# mini_rotation.net
KiCad netlist of a schematic drawn in EAGLE
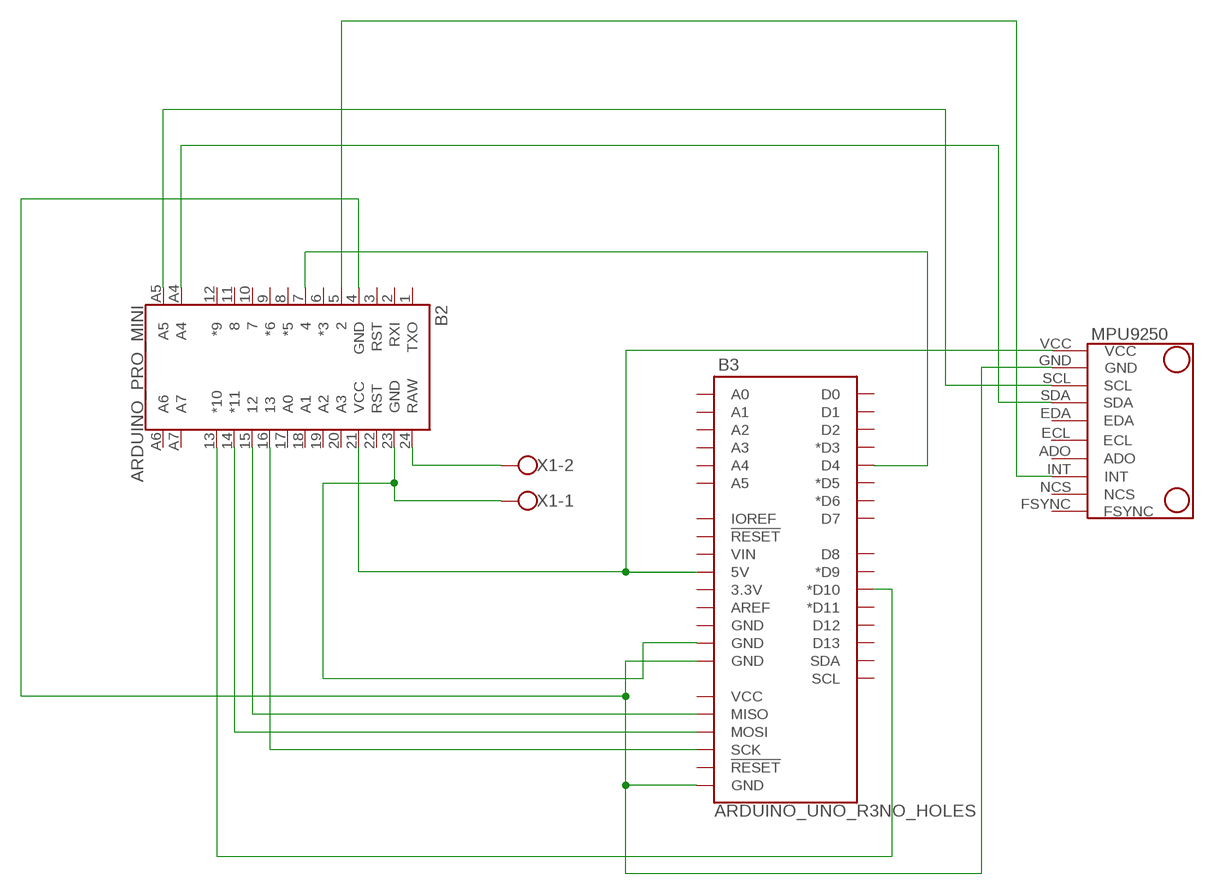
[diagram p0: schematic, sheet 1]

(export (version "E")
  (design (tool "Eeschema 10.0.6"))
  (components
    (comp (ref "B2")
      (value "ARDUINO_PRO_MINI")
      (footprint "eagle-import:ARDUINO_PRO_MINI")
      (libsource (lib "eagle-import") (part "ARDUINO_PRO_MINI"))
    )
    (comp (ref "B3")
      (value "ARDUINO_UNO_R3NO_HOLES")
      (footprint "eagle-import:ARDUINO_R3_NO_HOLES")
      (libsource (lib "eagle-import") (part "ARDUINO_UNO_R3NO_HOLES"))
    )
    (comp (ref "IC1")
      (value "MPU9250")
      (footprint "eagle-import:MPU9250")
      (libsource (lib "eagle-import") (part "MPU9250"))
    )
    (comp (ref "X1")
      (value "W237-102")
      (footprint "eagle-import:W237-102")
      (fields (field (name "MPN") "237-102"))
      (libsource (lib "eagle-import") (part "W237-102"))
    )
  )
  (nets
    (net (code "1") (name "Net-(B2-*10)") (class "Default")
      (node (ref "B2") (pin "13") (pinfunction "*10_13") (pintype "bidirectional"))
      (node (ref "B3") (pin "D10") (pinfunction "*D10_D10") (pintype "bidirectional"))
    )
    (net (code "2") (name "Net-(B2-*11)") (class "Default")
      (node (ref "B2") (pin "14") (pinfunction "*11_14") (pintype "bidirectional"))
      (node (ref "B3") (pin "MOSI") (pinfunction "MOSI_MOSI") (pintype "bidirectional"))
    )
    (net (code "3") (name "Net-(B2-2)") (class "Default")
      (node (ref "B2") (pin "5") (pinfunction "2_5") (pintype "bidirectional"))
      (node (ref "IC1") (pin "INT") (pinfunction "INT_INT") (pintype "bidirectional"))
    )
    (net (code "4") (name "Net-(B2-4)") (class "Default")
      (node (ref "B2") (pin "7") (pinfunction "4_7") (pintype "bidirectional"))
      (node (ref "B3") (pin "D4") (pinfunction "D4_D4") (pintype "bidirectional"))
    )
    (net (code "5") (name "Net-(B2-12)") (class "Default")
      (node (ref "B2") (pin "15") (pinfunction "12_15") (pintype "bidirectional"))
      (node (ref "B3") (pin "MISO") (pinfunction "MISO_MISO") (pintype "bidirectional"))
    )
    (net (code "6") (name "Net-(B2-13)") (class "Default")
      (node (ref "B2") (pin "16") (pinfunction "13_16") (pintype "bidirectional"))
      (node (ref "B3") (pin "SCK") (pinfunction "SCK_SCK") (pintype "bidirectional"))
    )
    (net (code "7") (name "Net-(B2-GND-Pad4)") (class "Default")
      (node (ref "B2") (pin "4") (pinfunction "GND_4") (pintype "power_in"))
      (node (ref "B3") (pin "GND@1") (pinfunction "GND_GND@1") (pintype "bidirectional"))
      (node (ref "B3") (pin "GND@2") (pinfunction "GND_GND@2") (pintype "bidirectional"))
      (node (ref "IC1") (pin "GND") (pinfunction "GND_GND") (pintype "bidirectional"))
    )
    (net (code "8") (name "Net-(B2-PadA4)") (class "Default")
      (node (ref "B2") (pin "A4") (pinfunction "A4_A4") (pintype "bidirectional"))
      (node (ref "IC1") (pin "SDA") (pinfunction "SDA_SDA") (pintype "bidirectional"))
    )
    (net (code "9") (name "Net-(B2-PadA5)") (class "Default")
      (node (ref "B2") (pin "A5") (pinfunction "A5_A5") (pintype "bidirectional"))
      (node (ref "IC1") (pin "SCL") (pinfunction "SCL_SCL") (pintype "bidirectional"))
    )
    (net (code "10") (name "Net-(B2-RAW)") (class "Default")
      (node (ref "B2") (pin "24") (pinfunction "RAW_24") (pintype "power_in"))
      (node (ref "X1") (pin "2") (pinfunction "KL_2") (pintype "passive"))
    )
    (net (code "11") (name "Net-(B2-VCC)") (class "Default")
      (node (ref "B2") (pin "21") (pinfunction "VCC_21") (pintype "power_in"))
      (node (ref "B3") (pin "5V") (pinfunction "5V_5V") (pintype "bidirectional"))
      (node (ref "IC1") (pin "VCC") (pinfunction "VCC_VCC") (pintype "bidirectional"))
    )
    (net (code "12") (name "Net-(X1A-KL)") (class "Default")
      (node (ref "B2") (pin "23") (pinfunction "GND_23") (pintype "power_in"))
      (node (ref "B3") (pin "GND@3") (pinfunction "GND_GND@3") (pintype "bidirectional"))
      (node (ref "X1") (pin "1") (pinfunction "KL_1") (pintype "passive"))
    )
    (net (code "13") (name "unconnected-(B2-*3-Pad6)") (class "Default")
      (node (ref "B2") (pin "6") (pinfunction "*3_6") (pintype "bidirectional"))
    )
    (net (code "14") (name "unconnected-(B2-*5-Pad8)") (class "Default")
      (node (ref "B2") (pin "8") (pinfunction "*5_8") (pintype "bidirectional"))
    )
    (net (code "15") (name "unconnected-(B2-*6-Pad9)") (class "Default")
      (node (ref "B2") (pin "9") (pinfunction "*6_9") (pintype "bidirectional"))
    )
    (net (code "16") (name "unconnected-(B2-*9-Pad12)") (class "Default")
      (node (ref "B2") (pin "12") (pinfunction "*9_12") (pintype "bidirectional"))
    )
    (net (code "17") (name "unconnected-(B2-7-Pad10)") (class "Default")
      (node (ref "B2") (pin "10") (pinfunction "7_10") (pintype "bidirectional"))
    )
    (net (code "18") (name "unconnected-(B2-8-Pad11)") (class "Default")
      (node (ref "B2") (pin "11") (pinfunction "8_11") (pintype "bidirectional"))
    )
    (net (code "19") (name "unconnected-(B2-A0-Pad17)") (class "Default")
      (node (ref "B2") (pin "17") (pinfunction "A0_17") (pintype "bidirectional"))
    )
    (net (code "20") (name "unconnected-(B2-A1-Pad18)") (class "Default")
      (node (ref "B2") (pin "18") (pinfunction "A1_18") (pintype "bidirectional"))
    )
    (net (code "21") (name "unconnected-(B2-A2-Pad19)") (class "Default")
      (node (ref "B2") (pin "19") (pinfunction "A2_19") (pintype "bidirectional"))
    )
    (net (code "22") (name "unconnected-(B2-A3-Pad20)") (class "Default")
      (node (ref "B2") (pin "20") (pinfunction "A3_20") (pintype "bidirectional"))
    )
    (net (code "23") (name "unconnected-(B2-PadA6)") (class "Default")
      (node (ref "B2") (pin "A6") (pinfunction "A6_A6") (pintype "bidirectional"))
    )
    (net (code "24") (name "unconnected-(B2-PadA7)") (class "Default")
      (node (ref "B2") (pin "A7") (pinfunction "A7_A7") (pintype "bidirectional"))
    )
    (net (code "25") (name "unconnected-(B2-RST-Pad3)") (class "Default")
      (node (ref "B2") (pin "3") (pinfunction "RST_3") (pintype "bidirectional"))
    )
    (net (code "26") (name "unconnected-(B2-RST-Pad22)") (class "Default")
      (node (ref "B2") (pin "22") (pinfunction "RST_22") (pintype "bidirectional"))
    )
    (net (code "27") (name "unconnected-(B2-RXI-Pad2)") (class "Default")
      (node (ref "B2") (pin "2") (pinfunction "RXI_2") (pintype "bidirectional"))
    )
    (net (code "28") (name "unconnected-(B2-TXO-Pad1)") (class "Default")
      (node (ref "B2") (pin "1") (pinfunction "TXO_1") (pintype "bidirectional"))
    )
    (net (code "29") (name "unconnected-(B3-*D3-PadD3)") (class "Default")
      (node (ref "B3") (pin "D3") (pinfunction "*D3_D3") (pintype "bidirectional"))
    )
    (net (code "30") (name "unconnected-(B3-*D5-PadD5)") (class "Default")
      (node (ref "B3") (pin "D5") (pinfunction "*D5_D5") (pintype "bidirectional"))
    )
    (net (code "31") (name "unconnected-(B3-*D6-PadD6)") (class "Default")
      (node (ref "B3") (pin "D6") (pinfunction "*D6_D6") (pintype "bidirectional"))
    )
    (net (code "32") (name "unconnected-(B3-*D9-PadD9)") (class "Default")
      (node (ref "B3") (pin "D9") (pinfunction "*D9_D9") (pintype "bidirectional"))
    )
    (net (code "33") (name "unconnected-(B3-*D11-PadD11)") (class "Default")
      (node (ref "B3") (pin "D11") (pinfunction "*D11_D11") (pintype "bidirectional"))
    )
    (net (code "34") (name "unconnected-(B3-GND-PadGND@4)") (class "Default")
      (node (ref "B3") (pin "GND@4") (pinfunction "GND_GND@4") (pintype "bidirectional"))
    )
    (net (code "35") (name "unconnected-(B3-Pad3.3V)") (class "Default")
      (node (ref "B3") (pin "3.3V") (pinfunction "3.3V_3.3V") (pintype "bidirectional"))
    )
    (net (code "36") (name "unconnected-(B3-PadA0)") (class "Default")
      (node (ref "B3") (pin "A0") (pinfunction "A0_A0") (pintype "bidirectional"))
    )
    (net (code "37") (name "unconnected-(B3-PadA1)") (class "Default")
      (node (ref "B3") (pin "A1") (pinfunction "A1_A1") (pintype "bidirectional"))
    )
    (net (code "38") (name "unconnected-(B3-PadA2)") (class "Default")
      (node (ref "B3") (pin "A2") (pinfunction "A2_A2") (pintype "bidirectional"))
    )
    (net (code "39") (name "unconnected-(B3-PadA3)") (class "Default")
      (node (ref "B3") (pin "A3") (pinfunction "A3_A3") (pintype "bidirectional"))
    )
    (net (code "40") (name "unconnected-(B3-PadA4)") (class "Default")
      (node (ref "B3") (pin "A4") (pinfunction "A4_A4") (pintype "bidirectional"))
    )
    (net (code "41") (name "unconnected-(B3-PadA5)") (class "Default")
      (node (ref "B3") (pin "A5") (pinfunction "A5_A5") (pintype "bidirectional"))
    )
    (net (code "42") (name "unconnected-(B3-PadAREF)") (class "Default")
      (node (ref "B3") (pin "AREF") (pinfunction "AREF_AREF") (pintype "bidirectional"))
    )
    (net (code "43") (name "unconnected-(B3-PadD0)") (class "Default")
      (node (ref "B3") (pin "D0") (pinfunction "D0_D0") (pintype "bidirectional"))
    )
    (net (code "44") (name "unconnected-(B3-PadD1)") (class "Default")
      (node (ref "B3") (pin "D1") (pinfunction "D1_D1") (pintype "bidirectional"))
    )
    (net (code "45") (name "unconnected-(B3-PadD2)") (class "Default")
      (node (ref "B3") (pin "D2") (pinfunction "D2_D2") (pintype "bidirectional"))
    )
    (net (code "46") (name "unconnected-(B3-PadD7)") (class "Default")
      (node (ref "B3") (pin "D7") (pinfunction "D7_D7") (pintype "bidirectional"))
    )
    (net (code "47") (name "unconnected-(B3-PadD8)") (class "Default")
      (node (ref "B3") (pin "D8") (pinfunction "D8_D8") (pintype "bidirectional"))
    )
    (net (code "48") (name "unconnected-(B3-PadD12)") (class "Default")
      (node (ref "B3") (pin "D12") (pinfunction "D12_D12") (pintype "bidirectional"))
    )
    (net (code "49") (name "unconnected-(B3-PadD13)") (class "Default")
      (node (ref "B3") (pin "D13") (pinfunction "D13_D13") (pintype "bidirectional"))
    )
    (net (code "50") (name "unconnected-(B3-PadIOREF)") (class "Default")
      (node (ref "B3") (pin "IOREF") (pinfunction "IOREF_IOREF") (pintype "bidirectional"))
    )
    (net (code "51") (name "unconnected-(B3-PadSCL)") (class "Default")
      (node (ref "B3") (pin "SCL") (pinfunction "SCL_SCL") (pintype "bidirectional"))
    )
    (net (code "52") (name "unconnected-(B3-PadSDA)") (class "Default")
      (node (ref "B3") (pin "SDA") (pinfunction "SDA_SDA") (pintype "bidirectional"))
    )
    (net (code "53") (name "unconnected-(B3-PadVCC)") (class "Default")
      (node (ref "B3") (pin "VCC") (pinfunction "VCC_VCC") (pintype "bidirectional"))
    )
    (net (code "54") (name "unconnected-(B3-PadVIN)") (class "Default")
      (node (ref "B3") (pin "VIN") (pinfunction "VIN_VIN") (pintype "bidirectional"))
    )
    (net (code "55") (name "unconnected-(B3-~{RESET}-PadRESET@1)") (class "Default")
      (node (ref "B3") (pin "RESET@1") (pinfunction "~{RESET}_RESET@1") (pintype "bidirectional"))
    )
    (net (code "56") (name "unconnected-(B3-~{RESET}-PadRESET@2)") (class "Default")
      (node (ref "B3") (pin "RESET@2") (pinfunction "~{RESET}_RESET@2") (pintype "bidirectional"))
    )
    (net (code "57") (name "unconnected-(IC1-PadADO)") (class "Default")
      (node (ref "IC1") (pin "ADO") (pinfunction "ADO_ADO") (pintype "bidirectional"))
    )
    (net (code "58") (name "unconnected-(IC1-PadECL)") (class "Default")
      (node (ref "IC1") (pin "ECL") (pinfunction "ECL_ECL") (pintype "bidirectional"))
    )
    (net (code "59") (name "unconnected-(IC1-PadEDA)") (class "Default")
      (node (ref "IC1") (pin "EDA") (pinfunction "EDA_EDA") (pintype "bidirectional"))
    )
    (net (code "60") (name "unconnected-(IC1-PadFSYNC)") (class "Default")
      (node (ref "IC1") (pin "FSYNC") (pinfunction "FSYNC_FSYNC") (pintype "bidirectional"))
    )
    (net (code "61") (name "unconnected-(IC1-PadNCS)") (class "Default")
      (node (ref "IC1") (pin "NCS") (pinfunction "NCS_NCS") (pintype "bidirectional"))
    )
  )
)
